# Sensing_-_HAL_Sensor.net
KiCad netlist of a schematic drawn in Altium Designer
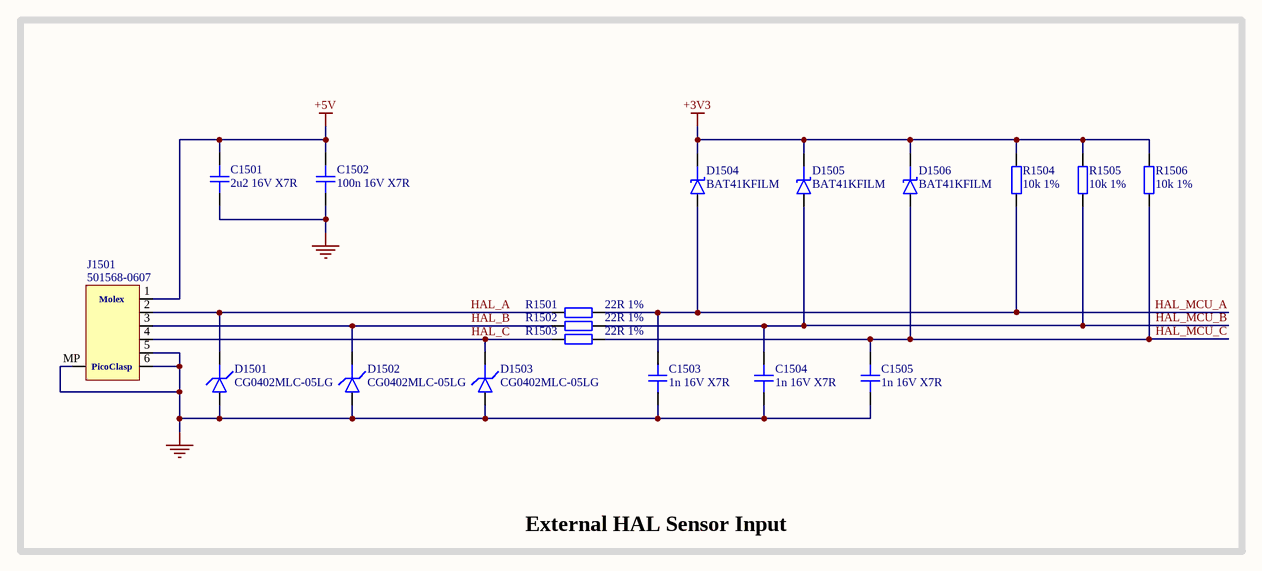
[diagram p0: Sensing - HAL Sensor.SchDoc]

(export (version "E")
  (design (tool "Eeschema 10.0.6"))
  (components
    (comp (ref "C1501")
      (value "2u2 16V X7R")
      (footprint "CAP_0603")
      (description "Capacitor SMD 0603")
      (fields
        (field (name "MANUFACTURER") "YAGEO")
        (field (name "MANUFACTURER PART NUMBER") "CC0603KRX7R7BB225")
      )
      (libsource (lib "Schematic-Lib-PhilsLab") (part "CAP_0603"))
    )
    (comp (ref "C1502")
      (value "100n 16V X7R")
      (footprint "CAP_0402")
      (description "Capacitor SMD 0402")
      (fields
        (field (name "MANUFACTURER") "YAGEO")
        (field (name "MANUFACTURER PART NUMBER") "CC0402JRX7R7BB104")
      )
      (libsource (lib "Schematic-Lib-PhilsLab") (part "CAP_0402"))
    )
    (comp (ref "C1503")
      (value "1n 16V X7R")
      (footprint "CAP_0402")
      (description "Capacitor SMD 0402")
      (fields
        (field (name "MANUFACTURER") "YAGEO")
        (field (name "MANUFACTURER PART NUMBER") "CC0402KRX7R7BB102")
      )
      (libsource (lib "Schematic-Lib-PhilsLab") (part "CAP_0402"))
    )
    (comp (ref "C1504")
      (value "1n 16V X7R")
      (footprint "CAP_0402")
      (description "Capacitor SMD 0402")
      (fields
        (field (name "MANUFACTURER") "YAGEO")
        (field (name "MANUFACTURER PART NUMBER") "CC0402KRX7R7BB102")
      )
      (libsource (lib "Schematic-Lib-PhilsLab") (part "CAP_0402"))
    )
    (comp (ref "C1505")
      (value "1n 16V X7R")
      (footprint "CAP_0402")
      (description "Capacitor SMD 0402")
      (fields
        (field (name "MANUFACTURER") "YAGEO")
        (field (name "MANUFACTURER PART NUMBER") "CC0402KRX7R7BB102")
      )
      (libsource (lib "Schematic-Lib-PhilsLab") (part "CAP_0402"))
    )
    (comp (ref "D1501")
      (value "CG0402MLC-05LG")
      (footprint "D_0402")
      (description "Diode TVS / ESD 0402")
      (fields (field (name "MANUFACTURER") "BOURNS"))
      (libsource (lib "Schematic-Lib-PhilsLab") (part "D_TVS_0402"))
    )
    (comp (ref "D1502")
      (value "CG0402MLC-05LG")
      (footprint "D_0402")
      (description "Diode TVS / ESD 0402")
      (libsource (lib "Schematic-Lib-PhilsLab") (part "D_TVS_0402"))
    )
    (comp (ref "D1503")
      (value "CG0402MLC-05LG")
      (footprint "D_0402")
      (description "Diode TVS / ESD 0402")
      (libsource (lib "Schematic-Lib-PhilsLab") (part "D_TVS_0402"))
    )
    (comp (ref "D1504")
      (value "BAT41KFILM")
      (footprint "SOD-523")
      (description "Diode Schottky SMD SOD-323")
      (fields (field (name "MANUFACTURER") "STMicroelectronics"))
      (libsource (lib "Schematic-Lib-PhilsLab") (part "D_SCHOTTKY_SOD_523"))
    )
    (comp (ref "D1505")
      (value "BAT41KFILM")
      (footprint "SOD-523")
      (description "Diode Schottky SMD SOD-323")
      (fields (field (name "MANUFACTURER") "STMicroelectronics"))
      (libsource (lib "Schematic-Lib-PhilsLab") (part "D_SCHOTTKY_SOD_523"))
    )
    (comp (ref "D1506")
      (value "BAT41KFILM")
      (footprint "SOD-523")
      (description "Diode Schottky SMD SOD-323")
      (fields (field (name "MANUFACTURER") "STMicroelectronics"))
      (libsource (lib "Schematic-Lib-PhilsLab") (part "D_SCHOTTKY_SOD_523"))
    )
    (comp (ref "J1501")
      (value "501568-0607")
      (footprint "501568-0607")
      (fields (field (name "MANUFACTURER") "Molex"))
      (libsource (lib "Schematic-Lib-PhilsLab") (part "501568-0607"))
    )
    (comp (ref "R1501")
      (value "22R 1%")
      (footprint "RES_0402")
      (description "Resistor SMD 0402")
      (fields
        (field (name "MANUFACTURER") "PANASONIC")
        (field (name "MANUFACTURER PART NUMBER") "ERJPA2F22R0X")
      )
      (libsource (lib "Schematic-Lib-PhilsLab") (part "RES_0402"))
    )
    (comp (ref "R1502")
      (value "22R 1%")
      (footprint "RES_0402")
      (description "Resistor SMD 0402")
      (fields
        (field (name "MANUFACTURER") "PANASONIC")
        (field (name "MANUFACTURER PART NUMBER") "ERJPA2F22R0X")
      )
      (libsource (lib "Schematic-Lib-PhilsLab") (part "RES_0402"))
    )
    (comp (ref "R1503")
      (value "22R 1%")
      (footprint "RES_0402")
      (description "Resistor SMD 0402")
      (fields
        (field (name "MANUFACTURER") "PANASONIC")
        (field (name "MANUFACTURER PART NUMBER") "ERJPA2F22R0X")
      )
      (libsource (lib "Schematic-Lib-PhilsLab") (part "RES_0402"))
    )
    (comp (ref "R1504")
      (value "10k 1%")
      (footprint "RES_0402")
      (description "Resistor SMD 0402")
      (fields
        (field (name "MANUFACTURER") "PANASONIC")
        (field (name "MANUFACTURER PART NUMBER") "ERJPA2F1002X")
      )
      (libsource (lib "Schematic-Lib-PhilsLab") (part "RES_0402"))
    )
    (comp (ref "R1505")
      (value "10k 1%")
      (footprint "RES_0402")
      (description "Resistor SMD 0402")
      (fields
        (field (name "MANUFACTURER") "PANASONIC")
        (field (name "MANUFACTURER PART NUMBER") "ERJPA2F1002X")
      )
      (libsource (lib "Schematic-Lib-PhilsLab") (part "RES_0402"))
    )
    (comp (ref "R1506")
      (value "10k 1%")
      (footprint "RES_0402")
      (description "Resistor SMD 0402")
      (fields
        (field (name "MANUFACTURER") "PANASONIC")
        (field (name "MANUFACTURER PART NUMBER") "ERJPA2F1002X")
      )
      (libsource (lib "Schematic-Lib-PhilsLab") (part "RES_0402"))
    )
  )
  (nets
    (net (code "1") (name "+3V3") (class "Default")
      (node (ref "D1504") (pin "K") (pinfunction "K_K") (pintype "passive"))
      (node (ref "D1505") (pin "K") (pinfunction "K_K") (pintype "passive"))
      (node (ref "D1506") (pin "K") (pinfunction "K_K") (pintype "passive"))
      (node (ref "R1504") (pin "2") (pinfunction "2_2") (pintype "passive"))
      (node (ref "R1505") (pin "2") (pinfunction "2_2") (pintype "passive"))
      (node (ref "R1506") (pin "2") (pinfunction "2_2") (pintype "passive"))
    )
    (net (code "2") (name "+5V") (class "Default")
      (node (ref "C1501") (pin "2") (pinfunction "2_2") (pintype "passive"))
      (node (ref "C1502") (pin "2") (pinfunction "2_2") (pintype "passive"))
      (node (ref "J1501") (pin "1") (pinfunction "1_1") (pintype "passive"))
    )
    (net (code "3") (name "/HAL_A") (class "Default")
      (node (ref "D1501") (pin "K") (pinfunction "K_K") (pintype "passive"))
      (node (ref "J1501") (pin "2") (pinfunction "2_2") (pintype "passive"))
      (node (ref "R1501") (pin "2") (pinfunction "2_2") (pintype "passive"))
    )
    (net (code "4") (name "/HAL_B") (class "Default")
      (node (ref "D1502") (pin "K") (pinfunction "K_K") (pintype "passive"))
      (node (ref "J1501") (pin "3") (pinfunction "3_3") (pintype "passive"))
      (node (ref "R1502") (pin "2") (pinfunction "2_2") (pintype "passive"))
    )
    (net (code "5") (name "/HAL_C") (class "Default")
      (node (ref "D1503") (pin "K") (pinfunction "K_K") (pintype "passive"))
      (node (ref "J1501") (pin "4") (pinfunction "4_4") (pintype "passive"))
      (node (ref "R1503") (pin "2") (pinfunction "2_2") (pintype "passive"))
    )
    (net (code "6") (name "/HAL_MCU_A") (class "Default")
      (node (ref "C1503") (pin "2") (pinfunction "2_2") (pintype "passive"))
      (node (ref "D1504") (pin "A") (pinfunction "A_A") (pintype "passive"))
      (node (ref "R1501") (pin "1") (pinfunction "1_1") (pintype "passive"))
      (node (ref "R1504") (pin "1") (pinfunction "1_1") (pintype "passive"))
    )
    (net (code "7") (name "/HAL_MCU_B") (class "Default")
      (node (ref "C1504") (pin "2") (pinfunction "2_2") (pintype "passive"))
      (node (ref "D1505") (pin "A") (pinfunction "A_A") (pintype "passive"))
      (node (ref "R1502") (pin "1") (pinfunction "1_1") (pintype "passive"))
      (node (ref "R1505") (pin "1") (pinfunction "1_1") (pintype "passive"))
    )
    (net (code "8") (name "/HAL_MCU_C") (class "Default")
      (node (ref "C1505") (pin "2") (pinfunction "2_2") (pintype "passive"))
      (node (ref "D1506") (pin "A") (pinfunction "A_A") (pintype "passive"))
      (node (ref "R1503") (pin "1") (pinfunction "1_1") (pintype "passive"))
      (node (ref "R1506") (pin "1") (pinfunction "1_1") (pintype "passive"))
    )
    (net (code "9") (name "GND") (class "Default")
      (node (ref "C1501") (pin "1") (pinfunction "1_1") (pintype "passive"))
      (node (ref "C1502") (pin "1") (pinfunction "1_1") (pintype "passive"))
      (node (ref "C1503") (pin "1") (pinfunction "1_1") (pintype "passive"))
      (node (ref "C1504") (pin "1") (pinfunction "1_1") (pintype "passive"))
      (node (ref "C1505") (pin "1") (pinfunction "1_1") (pintype "passive"))
      (node (ref "D1501") (pin "A") (pinfunction "A_A") (pintype "passive"))
      (node (ref "D1502") (pin "A") (pinfunction "A_A") (pintype "passive"))
      (node (ref "D1503") (pin "A") (pinfunction "A_A") (pintype "passive"))
      (node (ref "J1501") (pin "5") (pinfunction "5_5") (pintype "passive"))
      (node (ref "J1501") (pin "6") (pinfunction "6_6") (pintype "passive"))
      (node (ref "J1501") (pin "MP") (pinfunction "MP_MP") (pintype "passive"))
    )
  )
)
